# InkTime-SmartWatch.net
KiCad netlist of a schematic drawn in EAGLE
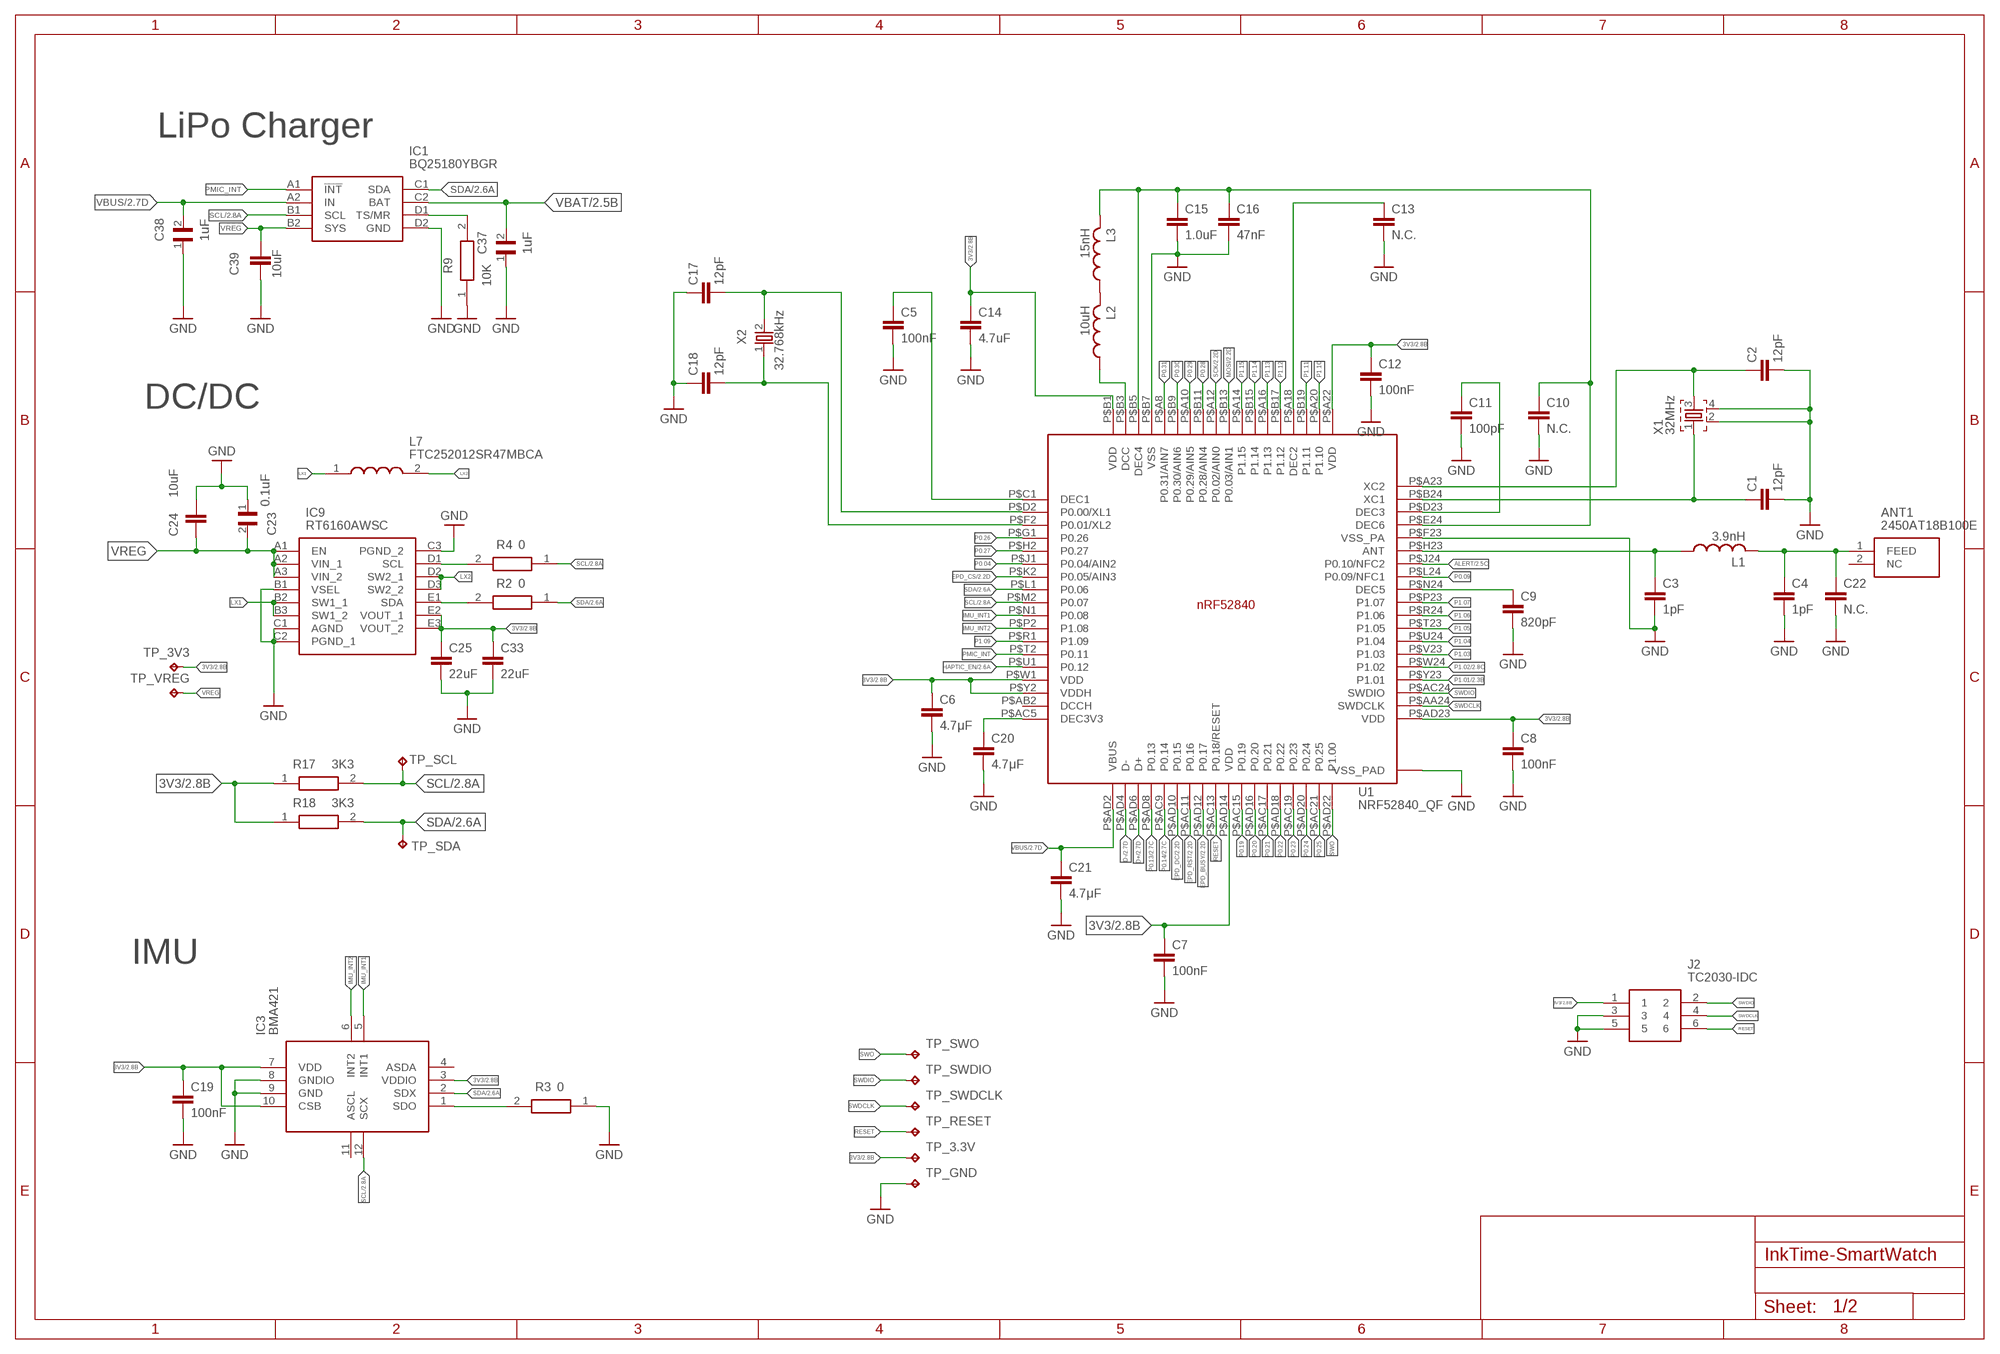
[diagram p0: schematic, sheet 1]
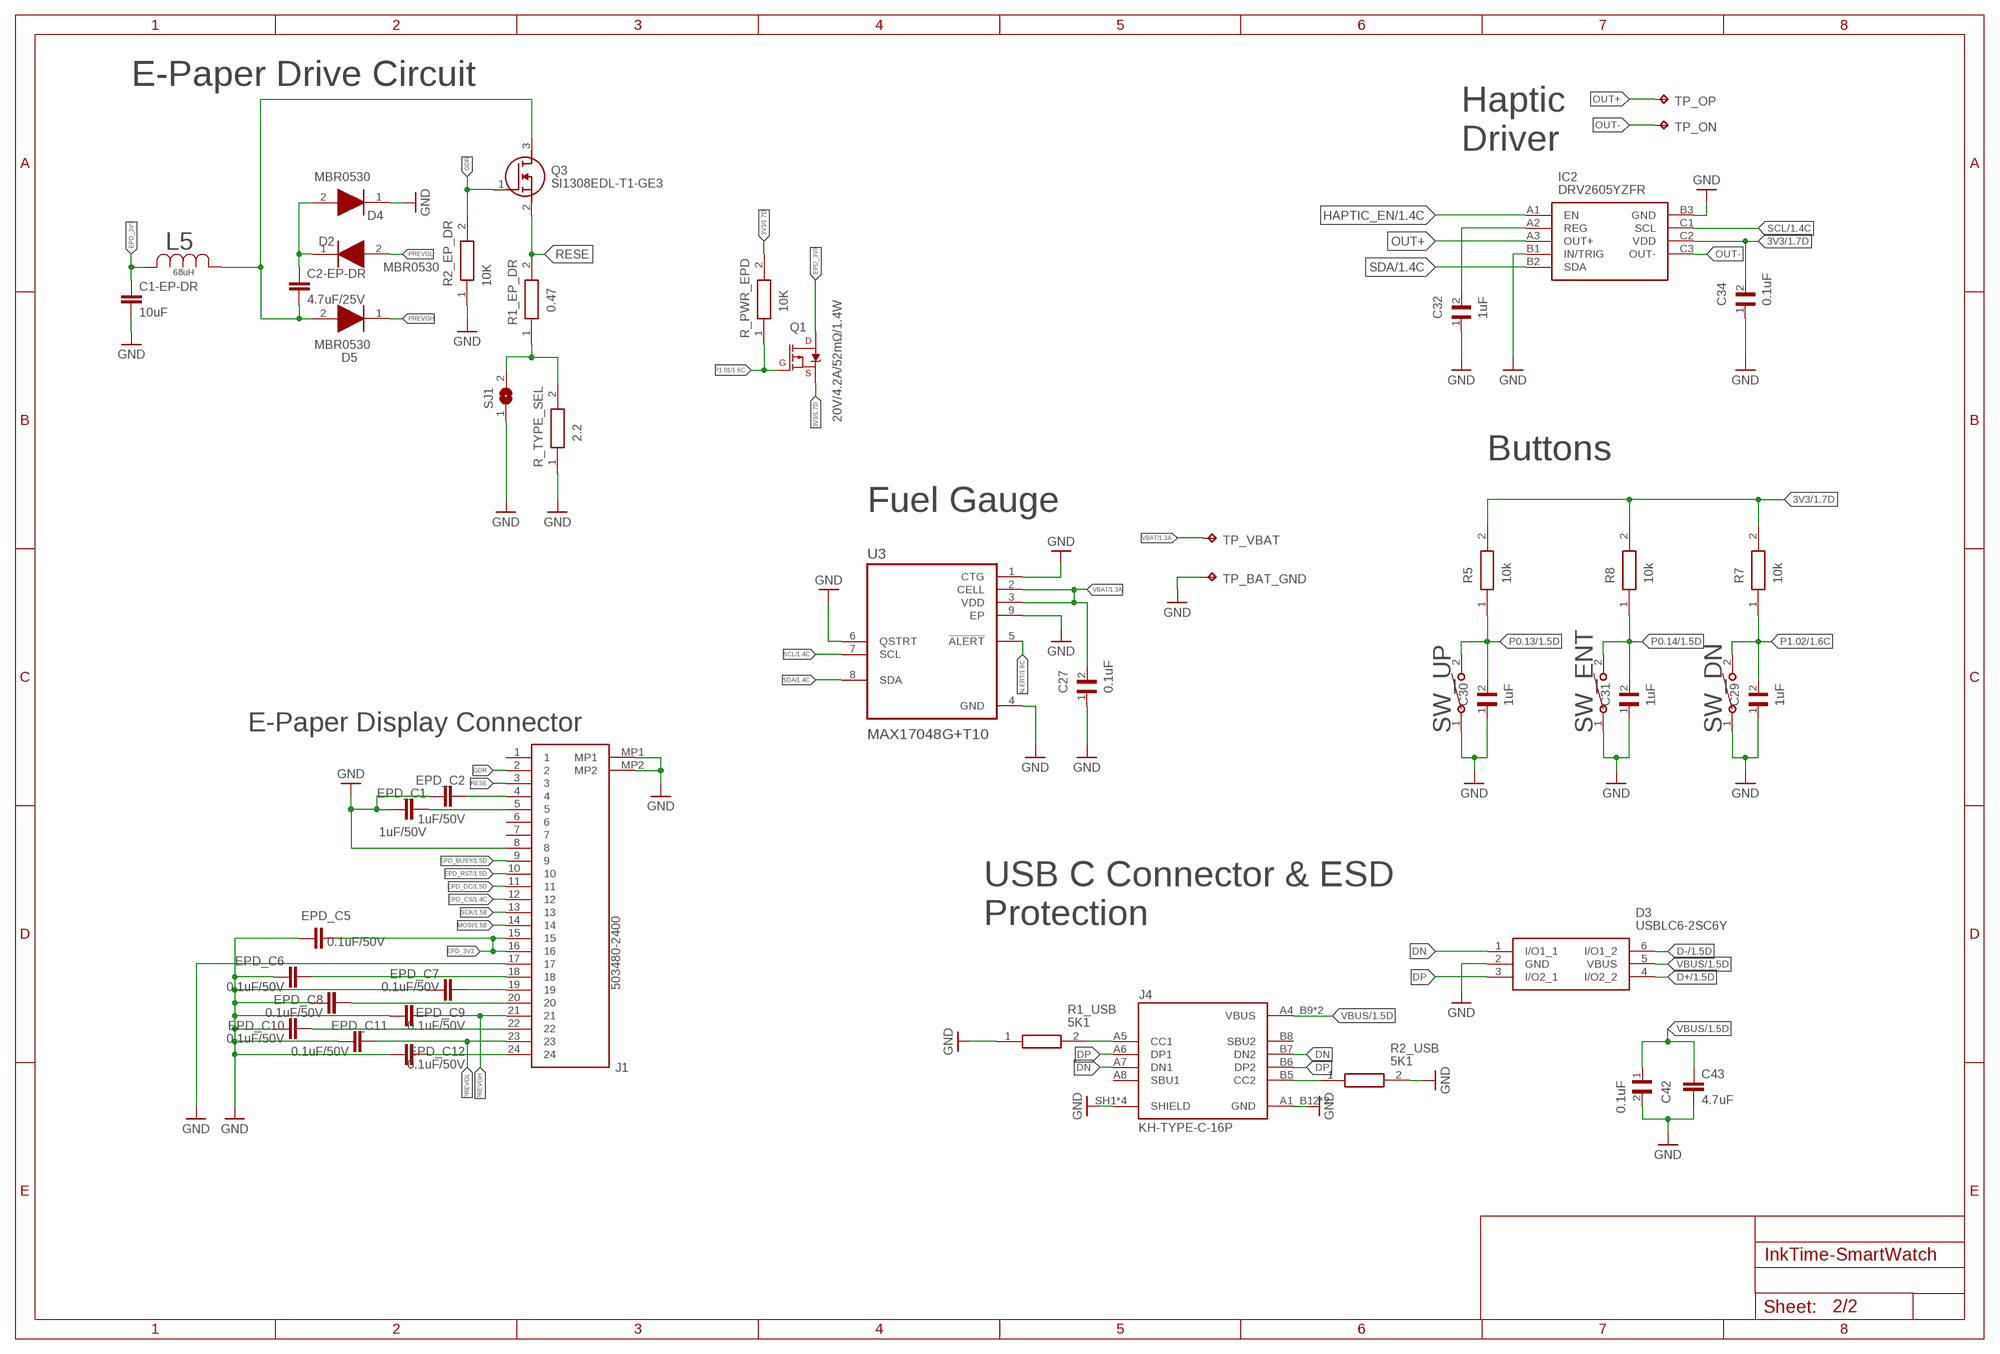
[diagram p1: schematic, sheet 2]

(export (version "E")
  (design (tool "Eeschema 10.0.6"))
  (components
    (comp (ref "C1-EP-DR")
      (value "10uF")
      (footprint "eagle-import:NORDIC_NRF_3_RESC0402_L")
      (libsource (lib "eagle-import") (part "NORDIC_NRF_3_CAPACITOR_0402_L"))
    )
    (comp (ref "C2-EP-DR")
      (value "4.7uF/25V")
      (footprint "eagle-import:NORDIC_NRF_3_RESC0402_L")
      (libsource (lib "eagle-import") (part "NORDIC_NRF_3_CAPACITOR_0402_L"))
    )
    (comp (ref "C27")
      (value "0.1uF")
      (footprint "eagle-import:GRM011R60J152KE01L_2_CAPC0201X13N")
      (fields (field (name "MF") "Murata") (field (name "MP") "GRM011R60J152KE01L"))
      (libsource (lib "eagle-import") (part "GRM011R60J152KE01L_2_GRM011R60J152KE01L"))
    )
    (comp (ref "C29")
      (value "1uF")
      (footprint "eagle-import:GRM011R60J152KE01L_2_CAPC0201X13N")
      (fields (field (name "MF") "Murata") (field (name "MP") "GRM011R60J152KE01L"))
      (libsource (lib "eagle-import") (part "GRM011R60J152KE01L_2_GRM011R60J152KE01L"))
    )
    (comp (ref "C30")
      (value "1uF")
      (footprint "eagle-import:GRM011R60J152KE01L_2_CAPC0201X13N")
      (fields (field (name "MF") "Murata") (field (name "MP") "GRM011R60J152KE01L"))
      (libsource (lib "eagle-import") (part "GRM011R60J152KE01L_2_GRM011R60J152KE01L"))
    )
    (comp (ref "C31")
      (value "1uF")
      (footprint "eagle-import:GRM011R60J152KE01L_2_CAPC0201X13N")
      (fields (field (name "MF") "Murata") (field (name "MP") "GRM011R60J152KE01L"))
      (libsource (lib "eagle-import") (part "GRM011R60J152KE01L_2_GRM011R60J152KE01L"))
    )
    (comp (ref "C32")
      (value "1uF")
      (footprint "eagle-import:GRM011R60J152KE01L_2_CAPC0201X13N")
      (fields (field (name "MF") "Murata") (field (name "MP") "GRM011R60J152KE01L"))
      (libsource (lib "eagle-import") (part "GRM011R60J152KE01L_2_GRM011R60J152KE01L"))
    )
    (comp (ref "C34")
      (value "0.1uF")
      (footprint "eagle-import:GRM011R60J152KE01L_2_CAPC0201X13N")
      (fields (field (name "MF") "Murata") (field (name "MP") "GRM011R60J152KE01L"))
      (libsource (lib "eagle-import") (part "GRM011R60J152KE01L_2_GRM011R60J152KE01L"))
    )
    (comp (ref "C42")
      (value "0.1uF")
      (footprint "eagle-import:GRM011R60J152KE01L_2_CAPC0201X13N")
      (fields (field (name "MF") "Murata") (field (name "MP") "GRM011R60J152KE01L"))
      (libsource (lib "eagle-import") (part "GRM011R60J152KE01L_2_GRM011R60J152KE01L"))
    )
    (comp (ref "C43")
      (value "4.7uF")
      (footprint "eagle-import:NORDIC_NRF_3_RESC0402_L")
      (libsource (lib "eagle-import") (part "NORDIC_NRF_3_CAPACITOR_0402_L"))
    )
    (comp (ref "D2")
      (value "MBR0530")
      (footprint "eagle-import:ESP32_C6_LIBRARY_5_SOD3716X135N")
      (fields (field (name "MF") "ON Semiconductor"))
      (libsource (lib "eagle-import") (part "ESP32_C6_LIBRARY_5_MBR0530"))
    )
    (comp (ref "D3")
      (value "USBLC6-2SC6Y")
      (footprint "eagle-import:ESP32_C6_LIBRARY_3_SOT95P280X145-6N")
      (fields (field (name "MF") "STMicroelectronics"))
      (libsource (lib "eagle-import") (part "ESP32_C6_LIBRARY_3_USBLC6-2SC6Y"))
    )
    (comp (ref "D4")
      (value "MBR0530")
      (footprint "eagle-import:ESP32_C6_LIBRARY_5_SOD3716X135N")
      (fields (field (name "MF") "ON Semiconductor"))
      (libsource (lib "eagle-import") (part "ESP32_C6_LIBRARY_5_MBR0530"))
    )
    (comp (ref "D5")
      (value "MBR0530")
      (footprint "eagle-import:ESP32_C6_LIBRARY_5_SOD3716X135N")
      (fields (field (name "MF") "ON Semiconductor"))
      (libsource (lib "eagle-import") (part "ESP32_C6_LIBRARY_5_MBR0530"))
    )
    (comp (ref "EPD_C1")
      (value "1uF/50V")
      (footprint "eagle-import:NORDIC_NRF_3_RESC0402_L")
      (libsource (lib "eagle-import") (part "NORDIC_NRF_3_CAPACITOR_0402_L"))
    )
    (comp (ref "EPD_C2")
      (value "1uF/50V")
      (footprint "eagle-import:NORDIC_NRF_3_RESC0402_L")
      (libsource (lib "eagle-import") (part "NORDIC_NRF_3_CAPACITOR_0402_L"))
    )
    (comp (ref "EPD_C5")
      (value "0.1uF/50V")
      (footprint "eagle-import:NORDIC_NRF_3_RESC0201_L")
      (libsource (lib "eagle-import") (part "NORDIC_NRF_3_CAPACITOR_0201_L"))
    )
    (comp (ref "EPD_C6")
      (value "0.1uF/50V")
      (footprint "eagle-import:NORDIC_NRF_3_RESC0402_L")
      (libsource (lib "eagle-import") (part "NORDIC_NRF_3_CAPACITOR_0402_L"))
    )
    (comp (ref "EPD_C7")
      (value "0.1uF/50V")
      (footprint "eagle-import:NORDIC_NRF_3_RESC0402_L")
      (libsource (lib "eagle-import") (part "NORDIC_NRF_3_CAPACITOR_0402_L"))
    )
    (comp (ref "EPD_C8")
      (value "0.1uF/50V")
      (footprint "eagle-import:NORDIC_NRF_3_RESC0402_L")
      (libsource (lib "eagle-import") (part "NORDIC_NRF_3_CAPACITOR_0402_L"))
    )
    (comp (ref "EPD_C9")
      (value "0.1uF/50V")
      (footprint "eagle-import:NORDIC_NRF_3_RESC0402_L")
      (libsource (lib "eagle-import") (part "NORDIC_NRF_3_CAPACITOR_0402_L"))
    )
    (comp (ref "EPD_C10")
      (value "0.1uF/50V")
      (footprint "eagle-import:NORDIC_NRF_3_RESC0402_L")
      (libsource (lib "eagle-import") (part "NORDIC_NRF_3_CAPACITOR_0402_L"))
    )
    (comp (ref "EPD_C11")
      (value "0.1uF/50V")
      (footprint "eagle-import:NORDIC_NRF_3_RESC0402_L")
      (libsource (lib "eagle-import") (part "NORDIC_NRF_3_CAPACITOR_0402_L"))
    )
    (comp (ref "EPD_C12")
      (value "0.1uF/50V")
      (footprint "eagle-import:NORDIC_NRF_3_RESC0402_L")
      (libsource (lib "eagle-import") (part "NORDIC_NRF_3_CAPACITOR_0402_L"))
    )
    (comp (ref "IC2")
      (value "DRV2605YZFR")
      (footprint "eagle-import:DRV2605YZFR_BGA9C50P3X3_144X144X62")
      (libsource (lib "eagle-import") (part "DRV2605YZFR_DRV2605YZFR"))
    )
    (comp (ref "J1")
      (value "503480-2400")
      (footprint "eagle-import:503480-2400_5034802400")
      (fields (field (name "MOUSER_PART_NUMBER") "538-503480-2400"))
      (libsource (lib "eagle-import") (part "503480-2400_503480-2400"))
    )
    (comp (ref "J4")
      (value "KH-TYPE-C-16P")
      (footprint "eagle-import:KH-TYPE-C-16P_KINGHELM_KH-TYPE-C-16P")
      (fields (field (name "MF") "kinghelm"))
      (libsource (lib "eagle-import") (part "KH-TYPE-C-16P_KH-TYPE-C-16P"))
    )
    (comp (ref "L5")
      (value "68uH")
      (footprint "eagle-import:ESP32_C6_LIBRARY_2_IND_4828-WE-TPC_WRE")
      (fields
        (field (name "MANUFACTURER_PART_NUMBER") "744043680")
        (field (name "COPYRIGHT") "Copyright (C) 2024 Ultra Librarian. All rights reserved.")
      )
      (libsource (lib "eagle-import") (part "ESP32_C6_LIBRARY_2_744043680IND_4828-WE-TPC_WRE"))
    )
    (comp (ref "Q1")
      (value "20V/4.2A/52mΩ/1.4W")
      (footprint "eagle-import:ESP32_C6_LIBRARY_4_ESP32_C6_LIBRARY_4_ESP32_C6_LIBRARY_4_ESP32_C6_LIBRARY_4_ESP32_WROVER_SPARKFUN-DISCRETESEMI_SOT23-3")
      (libsource (lib "eagle-import") (part "ESP32_C6_LIBRARY_4_ESP32_WROVER_SPARKFUN-DISCRETESEMI_MOSFET_PCH-DMG2305UX-7"))
    )
    (comp (ref "Q3")
      (value "SI1308EDL-T1-GE3")
      (footprint "eagle-import:ESP32_C6_LIBRARY_6_SOT65P210X110-3N")
      (fields (field (name "MF") "Vishay Siliconix"))
      (libsource (lib "eagle-import") (part "ESP32_C6_LIBRARY_6_SI1308EDL-T1-GE3"))
    )
    (comp (ref "R1_EP_DR")
      (value "0.47")
      (footprint "eagle-import:CPF0201D7K68C1_0201")
      (libsource (lib "eagle-import") (part "CPF0201D7K68C1_CPF0201D7K68C1"))
    )
    (comp (ref "R1_USB")
      (value "5K1")
      (footprint "eagle-import:CPF0201D7K68C1_0201")
      (libsource (lib "eagle-import") (part "CPF0201D7K68C1_CPF0201D7K68C1"))
    )
    (comp (ref "R2_EP_DR")
      (value "10K")
      (footprint "eagle-import:CPF0201D7K68C1_0201")
      (libsource (lib "eagle-import") (part "CPF0201D7K68C1_CPF0201D7K68C1"))
    )
    (comp (ref "R2_USB")
      (value "5K1")
      (footprint "eagle-import:CPF0201D7K68C1_0201")
      (libsource (lib "eagle-import") (part "CPF0201D7K68C1_CPF0201D7K68C1"))
    )
    (comp (ref "R5")
      (value "10k")
      (footprint "eagle-import:CPF0201D7K68C1_0201")
      (libsource (lib "eagle-import") (part "CPF0201D7K68C1_CPF0201D7K68C1"))
    )
    (comp (ref "R7")
      (value "10k")
      (footprint "eagle-import:CPF0201D7K68C1_0201")
      (libsource (lib "eagle-import") (part "CPF0201D7K68C1_CPF0201D7K68C1"))
    )
    (comp (ref "R8")
      (value "10k")
      (footprint "eagle-import:CPF0201D7K68C1_0201")
      (libsource (lib "eagle-import") (part "CPF0201D7K68C1_CPF0201D7K68C1"))
    )
    (comp (ref "R_PWR_EPD")
      (value "10K")
      (footprint "eagle-import:CPF0201D7K68C1_0201")
      (libsource (lib "eagle-import") (part "CPF0201D7K68C1_CPF0201D7K68C1"))
    )
    (comp (ref "R_TYPE_SEL")
      (value "2.2")
      (footprint "eagle-import:CPF0201D7K68C1_0201")
      (libsource (lib "eagle-import") (part "CPF0201D7K68C1_CPF0201D7K68C1"))
    )
    (comp (ref "SJ1")
      (value "ESP32_C6_LIBRARY_7_JUMPER_SJ")
      (footprint "eagle-import:ESP32_C6_LIBRARY_7_JUMPER_SJ")
      (libsource (lib "eagle-import") (part "ESP32_C6_LIBRARY_7_JUMPER_SJ"))
    )
    (comp (ref "SW_DN")
      (value "2025-10-22_07-23-44_LIBRARY_EVP-AKE31ASW_EVP-AKE31A_PAN")
      (footprint "eagle-import:2025-10-22_07-23-44_LIBRARY_SW_EVP-AKE31A_PAN")
      (fields
        (field (name "MANUFACTURER_PART_NUMBER") "EVP-AKE31A")
        (field (name "COPYRIGHT") "Copyright (C) 2025 Ultra Librarian. All rights reserved.")
      )
      (libsource (lib "eagle-import") (part "2025-10-22_07-23-44_LIBRARY_EVP-AKE31ASW_EVP-AKE31A_PAN"))
    )
    (comp (ref "SW_ENT")
      (value "2025-10-22_07-23-44_LIBRARY_EVP-AKE31ASW_EVP-AKE31A_PAN")
      (footprint "eagle-import:2025-10-22_07-23-44_LIBRARY_SW_EVP-AKE31A_PAN")
      (fields
        (field (name "MANUFACTURER_PART_NUMBER") "EVP-AKE31A")
        (field (name "COPYRIGHT") "Copyright (C) 2025 Ultra Librarian. All rights reserved.")
      )
      (libsource (lib "eagle-import") (part "2025-10-22_07-23-44_LIBRARY_EVP-AKE31ASW_EVP-AKE31A_PAN"))
    )
    (comp (ref "SW_UP")
      (value "2025-10-22_07-23-44_LIBRARY_EVP-AKE31ASW_EVP-AKE31A_PAN")
      (footprint "eagle-import:2025-10-22_07-23-44_LIBRARY_SW_EVP-AKE31A_PAN")
      (fields
        (field (name "MANUFACTURER_PART_NUMBER") "EVP-AKE31A")
        (field (name "COPYRIGHT") "Copyright (C) 2025 Ultra Librarian. All rights reserved.")
      )
      (libsource (lib "eagle-import") (part "2025-10-22_07-23-44_LIBRARY_EVP-AKE31ASW_EVP-AKE31A_PAN"))
    )
    (comp (ref "TP_BAT_GND")
      (value "HECTOR_WATCH_1_TPTP20R")
      (footprint "eagle-import:HECTOR_WATCH_1_TP20R")
      (libsource (lib "eagle-import") (part "HECTOR_WATCH_1_TPTP20R"))
    )
    (comp (ref "TP_ON")
      (value "HECTOR_WATCH_1_TPTP20R")
      (footprint "eagle-import:HECTOR_WATCH_1_TP20R")
      (libsource (lib "eagle-import") (part "HECTOR_WATCH_1_TPTP20R"))
    )
    (comp (ref "TP_OP")
      (value "HECTOR_WATCH_1_TPTP20R")
      (footprint "eagle-import:HECTOR_WATCH_1_TP20R")
      (libsource (lib "eagle-import") (part "HECTOR_WATCH_1_TPTP20R"))
    )
    (comp (ref "TP_VBAT")
      (value "HECTOR_WATCH_1_TPTP20R")
      (footprint "eagle-import:HECTOR_WATCH_1_TP20R")
      (libsource (lib "eagle-import") (part "HECTOR_WATCH_1_TPTP20R"))
    )
    (comp (ref "U3")
      (value "MAX17048G+T10")
      (footprint "eagle-import:ESP32_C6_LIBRARY_SON50P200X200X80-9N")
      (fields (field (name "MF") "Analog Devices"))
      (libsource (lib "eagle-import") (part "ESP32_C6_LIBRARY_MAX17048G+T10"))
    )
    (comp (ref "ANT1")
      (value "2450AT18B100E")
      (footprint "eagle-import:2450AT18B100E_ANTC3216X140N")
      (fields (field (name "MOUSER_PART_NUMBER") "609-2450AT18B100E"))
      (libsource (lib "eagle-import") (part "2450AT18B100E_2450AT18B100E"))
    )
    (comp (ref "C1")
      (value "12pF")
      (footprint "eagle-import:NORDIC_NRF_3_RESC0201_L")
      (libsource (lib "eagle-import") (part "NORDIC_NRF_3_CAPACITOR_0201_L"))
    )
    (comp (ref "C2")
      (value "12pF")
      (footprint "eagle-import:NORDIC_NRF_3_RESC0201_L")
      (libsource (lib "eagle-import") (part "NORDIC_NRF_3_CAPACITOR_0201_L"))
    )
    (comp (ref "C3")
      (value "1pF")
      (footprint "eagle-import:NORDIC_NRF_3_RESC0201_L")
      (libsource (lib "eagle-import") (part "NORDIC_NRF_3_CAPACITOR_0201_L"))
    )
    (comp (ref "C4")
      (value "1pF")
      (footprint "eagle-import:NORDIC_NRF_3_RESC0201_L")
      (libsource (lib "eagle-import") (part "NORDIC_NRF_3_CAPACITOR_0201_L"))
    )
    (comp (ref "C5")
      (value "100nF")
      (footprint "eagle-import:NORDIC_NRF_3_RESC0201_L")
      (libsource (lib "eagle-import") (part "NORDIC_NRF_3_CAPACITOR_0201_L"))
    )
    (comp (ref "C6")
      (value "4.7μF")
      (footprint "eagle-import:PERFECT_0402_0402")
      (libsource (lib "eagle-import") (part "PERFECT_0402_CAP_0402"))
    )
    (comp (ref "C7")
      (value "100nF")
      (footprint "eagle-import:NORDIC_NRF_3_RESC0201_L")
      (libsource (lib "eagle-import") (part "NORDIC_NRF_3_CAPACITOR_0201_L"))
    )
    (comp (ref "C8")
      (value "100nF")
      (footprint "eagle-import:NORDIC_NRF_3_RESC0201_L")
      (libsource (lib "eagle-import") (part "NORDIC_NRF_3_CAPACITOR_0201_L"))
    )
    (comp (ref "C9")
      (value "820pF")
      (footprint "eagle-import:NORDIC_NRF_3_RESC0201_L")
      (libsource (lib "eagle-import") (part "NORDIC_NRF_3_CAPACITOR_0201_L"))
    )
    (comp (ref "C10")
      (value "N.C.")
      (footprint "eagle-import:NORDIC_NRF_3_RESC0201_L")
      (libsource (lib "eagle-import") (part "NORDIC_NRF_3_CAPACITOR_0201_L"))
    )
    (comp (ref "C11")
      (value "100pF")
      (footprint "eagle-import:NORDIC_NRF_3_RESC0201_L")
      (libsource (lib "eagle-import") (part "NORDIC_NRF_3_CAPACITOR_0201_L"))
    )
    (comp (ref "C12")
      (value "100nF")
      (footprint "eagle-import:NORDIC_NRF_3_RESC0201_L")
      (libsource (lib "eagle-import") (part "NORDIC_NRF_3_CAPACITOR_0201_L"))
    )
    (comp (ref "C13")
      (value "N.C.")
      (footprint "eagle-import:NORDIC_NRF_3_RESC0201_L")
      (libsource (lib "eagle-import") (part "NORDIC_NRF_3_CAPACITOR_0201_L"))
    )
    (comp (ref "C14")
      (value "4.7uF")
      (footprint "eagle-import:NORDIC_NRF_3_RESC0402_L")
      (libsource (lib "eagle-import") (part "NORDIC_NRF_3_CAPACITOR_0402_L"))
    )
    (comp (ref "C15")
      (value "1.0uF")
      (footprint "eagle-import:PERFECT_0402_0402")
      (libsource (lib "eagle-import") (part "PERFECT_0402_CAP_0402"))
    )
    (comp (ref "C16")
      (value "47nF")
      (footprint "eagle-import:PERFECT_0402_0402")
      (libsource (lib "eagle-import") (part "PERFECT_0402_CAP_0402"))
    )
    (comp (ref "C17")
      (value "12pF")
      (footprint "eagle-import:NORDIC_NRF_3_RESC0201_L")
      (libsource (lib "eagle-import") (part "NORDIC_NRF_3_CAPACITOR_0201_L"))
    )
    (comp (ref "C18")
      (value "12pF")
      (footprint "eagle-import:NORDIC_NRF_3_RESC0201_L")
      (libsource (lib "eagle-import") (part "NORDIC_NRF_3_CAPACITOR_0201_L"))
    )
    (comp (ref "C19")
      (value "100nF")
      (footprint "eagle-import:NORDIC_NRF_3_RESC0201_L")
      (libsource (lib "eagle-import") (part "NORDIC_NRF_3_CAPACITOR_0201_L"))
    )
    (comp (ref "C20")
      (value "4.7μF")
      (footprint "eagle-import:PERFECT_0402_0402")
      (libsource (lib "eagle-import") (part "PERFECT_0402_CAP_0402"))
    )
    (comp (ref "C21")
      (value "4.7μF")
      (footprint "eagle-import:PERFECT_0402_0402")
      (libsource (lib "eagle-import") (part "PERFECT_0402_CAP_0402"))
    )
    (comp (ref "C22")
      (value "N.C.")
      (footprint "eagle-import:NORDIC_NRF_3_RESC0201_L")
      (libsource (lib "eagle-import") (part "NORDIC_NRF_3_CAPACITOR_0201_L"))
    )
    (comp (ref "C23")
      (value "0.1uF")
      (footprint "eagle-import:GRM011R60J152KE01L_2_CAPC0201X13N")
      (fields (field (name "MF") "Murata") (field (name "MP") "GRM011R60J152KE01L"))
      (libsource (lib "eagle-import") (part "GRM011R60J152KE01L_2_GRM011R60J152KE01L"))
    )
    (comp (ref "C24")
      (value "10uF")
      (footprint "eagle-import:PERFECT_0402_0402")
      (libsource (lib "eagle-import") (part "PERFECT_0402_CAP_0402"))
    )
    (comp (ref "C25")
      (value "22uF")
      (footprint "eagle-import:PERFECT_0402_0402")
      (libsource (lib "eagle-import") (part "PERFECT_0402_CAP_0402"))
    )
    (comp (ref "C33")
      (value "22uF")
      (footprint "eagle-import:PERFECT_0402_0402")
      (libsource (lib "eagle-import") (part "PERFECT_0402_CAP_0402"))
    )
    (comp (ref "C37")
      (value "1uF")
      (footprint "eagle-import:GRM011R60J152KE01L_2_CAPC0201X13N")
      (fields (field (name "MF") "Murata") (field (name "MP") "GRM011R60J152KE01L"))
      (libsource (lib "eagle-import") (part "GRM011R60J152KE01L_2_GRM011R60J152KE01L"))
    )
    (comp (ref "C38")
      (value "1uF")
      (footprint "eagle-import:GRM011R60J152KE01L_2_CAPC0201X13N")
      (fields (field (name "MF") "Murata") (field (name "MP") "GRM011R60J152KE01L"))
      (libsource (lib "eagle-import") (part "GRM011R60J152KE01L_2_GRM011R60J152KE01L"))
    )
    (comp (ref "C39")
      (value "10uF")
      (footprint "eagle-import:PERFECT_0402_0402")
      (libsource (lib "eagle-import") (part "PERFECT_0402_CAP_0402"))
    )
    (comp (ref "IC1")
      (value "BQ25180YBGR")
      (footprint "eagle-import:BQ25180YBGR_BGA8C40P2X4_100X155X50")
      (fields (field (name "MOUSER_PART_NUMBER") "595-BQ25180YBGR"))
      (libsource (lib "eagle-import") (part "BQ25180YBGR_BQ25180YBGR"))
    )
    (comp (ref "IC3")
      (value "BMA421")
      (footprint "eagle-import:BMA423_BMA423")
      (fields (field (name "ARROW_PART_NUMBER") "BMA423") (field (name "MOUSER_PART_NUMBER") "262-BMA423"))
      (libsource (lib "eagle-import") (part "BMA423_BMA423"))
    )
    (comp (ref "IC9")
      (value "RT6160AWSC")
      (footprint "eagle-import:RT6160AWSC_BGA15C40P3X5_140X230X60")
      (fields (field (name "MOUSER_PART_NUMBER") "835-RT6160AWSC"))
      (libsource (lib "eagle-import") (part "RT6160AWSC_RT6160AWSC"))
    )
    (comp (ref "J2")
      (value "TC2030-IDC")
      (footprint "eagle-import:TC2030-IDC_TC2030IDC")
      (libsource (lib "eagle-import") (part "TC2030-IDC_TC2030-IDC"))
    )
    (comp (ref "L1")
      (value "3.9nH")
      (footprint "eagle-import:NORDIC_NRF_2_RESC0402_L")
      (libsource (lib "eagle-import") (part "NORDIC_NRF_2_INDUCTOR_0402_L"))
    )
    (comp (ref "L2")
      (value "10uH")
      (footprint "eagle-import:NORDIC_NRF_2_RESC0402_L")
      (libsource (lib "eagle-import") (part "NORDIC_NRF_2_INDUCTOR_0402_L"))
    )
    (comp (ref "L3")
      (value "15nH")
      (footprint "eagle-import:NORDIC_NRF_2_RESC0402_L")
      (libsource (lib "eagle-import") (part "NORDIC_NRF_2_INDUCTOR_0402_L"))
    )
    (comp (ref "L7")
      (value "FTC252012SR47MBCA")
      (footprint "eagle-import:MLP2016SR47MT0S1_INDC2016X100N")
      (libsource (lib "eagle-import") (part "MLP2016SR47MT0S1_FTC252012SR47MBCA"))
    )
    (comp (ref "R2")
      (value "0")
      (footprint "eagle-import:CPF0201D7K68C1_0201")
      (libsource (lib "eagle-import") (part "CPF0201D7K68C1_CPF0201D7K68C1"))
    )
    (comp (ref "R3")
      (value "0")
      (footprint "eagle-import:CPF0201D7K68C1_0201")
      (libsource (lib "eagle-import") (part "CPF0201D7K68C1_CPF0201D7K68C1"))
    )
    (comp (ref "R4")
      (value "0")
      (footprint "eagle-import:CPF0201D7K68C1_0201")
      (libsource (lib "eagle-import") (part "CPF0201D7K68C1_CPF0201D7K68C1"))
    )
    (comp (ref "R9")
      (value "10K")
      (footprint "eagle-import:CPF0201D7K68C1_0201")
      (libsource (lib "eagle-import") (part "CPF0201D7K68C1_CPF0201D7K68C1"))
    )
    (comp (ref "R17")
      (value "3K3")
      (footprint "eagle-import:CPF0201D7K68C1_0201")
      (libsource (lib "eagle-import") (part "CPF0201D7K68C1_CPF0201D7K68C1"))
    )
    (comp (ref "R18")
      (value "3K3")
      (footprint "eagle-import:CPF0201D7K68C1_0201")
      (libsource (lib "eagle-import") (part "CPF0201D7K68C1_CPF0201D7K68C1"))
    )
    (comp (ref "TP_3.3V")
      (value "HECTOR_WATCH_1_TPTP20R")
      (footprint "eagle-import:HECTOR_WATCH_1_TP20R")
      (libsource (lib "eagle-import") (part "HECTOR_WATCH_1_TPTP20R"))
    )
    (comp (ref "TP_3V3")
      (value "HECTOR_WATCH_1_TPTP20R")
      (footprint "eagle-import:HECTOR_WATCH_1_TP20R")
      (libsource (lib "eagle-import") (part "HECTOR_WATCH_1_TPTP20R"))
    )
    (comp (ref "TP_GND")
      (value "HECTOR_WATCH_1_TPTP20R")
      (footprint "eagle-import:HECTOR_WATCH_1_TP20R")
      (libsource (lib "eagle-import") (part "HECTOR_WATCH_1_TPTP20R"))
    )
    (comp (ref "TP_RESET")
      (value "HECTOR_WATCH_1_TPTP20R")
      (footprint "eagle-import:HECTOR_WATCH_1_TP20R")
      (libsource (lib "eagle-import") (part "HECTOR_WATCH_1_TPTP20R"))
    )
    (comp (ref "TP_SCL")
      (value "HECTOR_WATCH_1_TPTP20R")
      (footprint "eagle-import:HECTOR_WATCH_1_TP20R")
      (libsource (lib "eagle-import") (part "HECTOR_WATCH_1_TPTP20R"))
    )
    (comp (ref "TP_SDA")
      (value "HECTOR_WATCH_1_TPTP20R")
      (footprint "eagle-import:HECTOR_WATCH_1_TP20R")
      (libsource (lib "eagle-import") (part "HECTOR_WATCH_1_TPTP20R"))
    )
    (comp (ref "TP_SWDCLK")
      (value "HECTOR_WATCH_1_TPTP20R")
      (footprint "eagle-import:HECTOR_WATCH_1_TP20R")
      (libsource (lib "eagle-import") (part "HECTOR_WATCH_1_TPTP20R"))
    )
    (comp (ref "TP_SWDIO")
      (value "HECTOR_WATCH_1_TPTP20R")
      (footprint "eagle-import:HECTOR_WATCH_1_TP20R")
      (libsource (lib "eagle-import") (part "HECTOR_WATCH_1_TPTP20R"))
    )
    (comp (ref "TP_SWO")
      (value "HECTOR_WATCH_1_TPTP20R")
      (footprint "eagle-import:HECTOR_WATCH_1_TP20R")
      (libsource (lib "eagle-import") (part "HECTOR_WATCH_1_TPTP20R"))
    )
    (comp (ref "TP_VREG")
      (value "HECTOR_WATCH_1_TPTP20R")
      (footprint "eagle-import:HECTOR_WATCH_1_TP20R")
      (libsource (lib "eagle-import") (part "HECTOR_WATCH_1_TPTP20R"))
    )
    (comp (ref "U1")
      (value "NRF52840_QF")
      (footprint "eagle-import:NORDIC_NRF_4_AQFN50P700X700X85_HS-74N")
      (libsource (lib "eagle-import") (part "NORDIC_NRF_4_NRF52840_QF"))
    )
    (comp (ref "X1")
      (value "32MHz")
      (footprint "eagle-import:NORDIC_NRF_BT-XTAL_2016_N")
      (libsource (lib "eagle-import") (part "NORDIC_NRF_XTAL_32MHZ"))
    )
    (comp (ref "X2")
      (value "32.768kHz")
      (footprint "eagle-import:NORDIC_NRF_1_XTAL_3215_N")
      (libsource (lib "eagle-import") (part "NORDIC_NRF_1_XTAL_32KHZ"))
    )
  )
  (nets
    (net (code "1") (name "3V3") (class "Default")
      (node (ref "C12") (pin "1") (pinfunction "1_1") (pintype "passive"))
      (node (ref "C14") (pin "1") (pinfunction "1_1") (pintype "passive"))
      (node (ref "C19") (pin "1") (pinfunction "1_1") (pintype "passive"))
      (node (ref "C25") (pin "1") (pinfunction "1_1") (pintype "passive"))
      (node (ref "C33") (pin "1") (pinfunction "1_1") (pintype "passive"))
      (node (ref "C34") (pin "2") (pinfunction "2_2") (pintype "passive"))
      (node (ref "C6") (pin "1") (pinfunction "1_1") (pintype "passive"))
      (node (ref "C7") (pin "1") (pinfunction "1_1") (pintype "passive"))
      (node (ref "C8") (pin "1") (pinfunction "1_1") (pintype "passive"))
      (node (ref "IC2") (pin "C2") (pinfunction "VDD_C2") (pintype "bidirectional"))
      (node (ref "IC3") (pin "10") (pinfunction "CSB_10") (pintype "bidirectional"))
      (node (ref "IC3") (pin "3") (pinfunction "VDDIO_3") (pintype "bidirectional"))
      (node (ref "IC3") (pin "7") (pinfunction "VDD_7") (pintype "bidirectional"))
      (node (ref "IC9") (pin "E2") (pinfunction "VOUT_1_E2") (pintype "bidirectional"))
      (node (ref "IC9") (pin "E3") (pinfunction "VOUT_2_E3") (pintype "bidirectional"))
      (node (ref "J2") (pin "1") (pinfunction "1_1") (pintype "bidirectional"))
      (node (ref "Q1") (pin "2") (pinfunction "S_2") (pintype "bidirectional"))
      (node (ref "R17") (pin "1") (pinfunction "1_1") (pintype "bidirectional"))
      (node (ref "R18") (pin "1") (pinfunction "1_1") (pintype "bidirectional"))
      (node (ref "R5") (pin "2") (pinfunction "2_2") (pintype "bidirectional"))
      (node (ref "R7") (pin "2") (pinfunction "2_2") (pintype "bidirectional"))
      (node (ref "R8") (pin "2") (pinfunction "2_2") (pintype "bidirectional"))
      (node (ref "R_PWR_EPD") (pin "2") (pinfunction "2_2") (pintype "bidirectional"))
      (node (ref "TP_3.3V") (pin "TP") (pinfunction "TP_TP") (pintype "input"))
      (node (ref "TP_3V3") (pin "TP") (pinfunction "TP_TP") (pintype "input"))
      (node (ref "U1") (pin "P$A22") (pinfunction "VDD_P$A22") (pintype "power_in"))
      (node (ref "U1") (pin "P$AD14") (pinfunction "VDD_P$AD14") (pintype "power_in"))
      (node (ref "U1") (pin "P$AD23") (pinfunction "VDD_P$AD23") (pintype "power_in"))
      (node (ref "U1") (pin "P$B1") (pinfunction "VDD_P$B1") (pintype "power_in"))
      (node (ref "U1") (pin "P$W1") (pinfunction "VDD_P$W1") (pintype "power_in"))
      (node (ref "U1") (pin "P$Y2") (pinfunction "VDDH_P$Y2") (pintype "power_in"))
    )
    (net (code "2") (name "ALERT") (class "Default")
      (node (ref "U1") (pin "P$J24") (pinfunction "P0.10/NFC2_P$J24") (pintype "bidirectional"))
      (node (ref "U3") (pin "5") (pinfunction "~{ALERT}_5") (pintype "output"))
    )
    (net (code "3") (name "D+") (class "Default")
      (node (ref "D3") (pin "4") (pinfunction "I/O2_2_4") (pintype "bidirectional"))
      (node (ref "U1") (pin "P$AD6") (pinfunction "D+_P$AD6") (pintype "bidirectional"))
    )
    (net (code "4") (name "D-") (class "Default")
      (node (ref "D3") (pin "6") (pinfunction "I/O1_2_6") (pintype "bidirectional"))
      (node (ref "U1") (pin "P$AD4") (pinfunction "D-_P$AD4") (pintype "bidirectional"))
    )
    (net (code "5") (name "DN") (class "Default")
      (node (ref "D3") (pin "1") (pinfunction "I/O1_1_1") (pintype "bidirectional"))
      (node (ref "J4") (pin "A7") (pinfunction "DN1_A7") (pintype "bidirectional"))
      (node (ref "J4") (pin "B7") (pinfunction "DN2_B7") (pintype "bidirectional"))
    )
    (net (code "6") (name "DP") (class "Default")
      (node (ref "D3") (pin "3") (pinfunction "I/O2_1_3") (pintype "bidirectional"))
      (node (ref "J4") (pin "A6") (pinfunction "DP1_A6") (pintype "bidirectional"))
      (node (ref "J4") (pin "B6") (pinfunction "DP2_B6") (pintype "bidirectional"))
    )
    (net (code "7") (name "EPD_3V3") (class "Default")
      (node (ref "C1-EP-DR") (pin "1") (pinfunction "1_1") (pintype "passive"))
      (node (ref "EPD_C5") (pin "1") (pinfunction "1_1") (pintype "passive"))
      (node (ref "J1") (pin "15") (pinfunction "15_15") (pintype "bidirectional"))
      (node (ref "J1") (pin "16") (pinfunction "16_16") (pintype "bidirectional"))
      (node (ref "L5") (pin "2") (pinfunction "2_2") (pintype "passive"))
      (node (ref "Q1") (pin "3") (pinfunction "D_3") (pintype "bidirectional"))
    )
    (net (code "8") (name "EPD_BUSY") (class "Default")
      (node (ref "J1") (pin "9") (pinfunction "9_9") (pintype "bidirectional"))
      (node (ref "U1") (pin "P$AD12") (pinfunction "P0.17_P$AD12") (pintype "bidirectional"))
    )
    (net (code "9") (name "EPD_CS") (class "Default")
      (node (ref "J1") (pin "12") (pinfunction "12_12") (pintype "bidirectional"))
      (node (ref "U1") (pin "P$K2") (pinfunction "P0.05/AIN3_P$K2") (pintype "bidirectional"))
    )
    (net (code "10") (name "EPD_DC") (class "Default")
      (node (ref "J1") (pin "11") (pinfunction "11_11") (pintype "bidirectional"))
      (node (ref "U1") (pin "P$AD10") (pinfunction "P0.15_P$AD10") (pintype "bidirectional"))
    )
    (net (code "11") (name "EPD_RST") (class "Default")
      (node (ref "J1") (pin "10") (pinfunction "10_10") (pintype "bidirectional"))
      (node (ref "U1") (pin "P$AC11") (pinfunction "P0.16_P$AC11") (pintype "bidirectional"))
    )
    (net (code "12") (name "GDR") (class "Default")
      (node (ref "J1") (pin "2") (pinfunction "2_2") (pintype "bidirectional"))
      (node (ref "Q3") (pin "1") (pinfunction "G_1") (pintype "bidirectional"))
      (node (ref "R2_EP_DR") (pin "2") (pinfunction "2_2") (pintype "bidirectional"))
    )
    (net (code "13") (name "GND") (class "Default")
      (node (ref "C1") (pin "2") (pinfunction "2_2") (pintype "passive"))
      (node (ref "C1-EP-DR") (pin "2") (pinfunction "2_2") (pintype "passive"))
      (node (ref "C10") (pin "2") (pinfunction "2_2") (pintype "passive"))
      (node (ref "C11") (pin "2") (pinfunction "2_2") (pintype "passive"))
      (node (ref "C12") (pin "2") (pinfunction "2_2") (pintype "passive"))
      (node (ref "C13") (pin "2") (pinfunction "2_2") (pintype "passive"))
      (node (ref "C14") (pin "2") (pinfunction "2_2") (pintype "passive"))
      (node (ref "C15") (pin "2") (pinfunction "2_2") (pintype "passive"))
      (node (ref "C16") (pin "2") (pinfunction "2_2") (pintype "passive"))
      (node (ref "C17") (pin "1") (pinfunction "1_1") (pintype "passive"))
      (node (ref "C18") (pin "1") (pinfunction "1_1") (pintype "passive"))
      (node (ref "C19") (pin "2") (pinfunction "2_2") (pintype "passive"))
      (node (ref "C2") (pin "2") (pinfunction "2_2") (pintype "passive"))
      (node (ref "C20") (pin "2") (pinfunction "2_2") (pintype "passive"))
      (node (ref "C21") (pin "2") (pinfunction "2_2") (pintype "passive"))
      (node (ref "C22") (pin "2") (pinfunction "2_2") (pintype "passive"))
      (node (ref "C23") (pin "1") (pinfunction "1_1") (pintype "passive"))
      (node (ref "C24") (pin "1") (pinfunction "1_1") (pintype "passive"))
      (node (ref "C25") (pin "2") (pinfunction "2_2") (pintype "passive"))
      (node (ref "C27") (pin "1") (pinfunction "1_1") (pintype "passive"))
      (node (ref "C29") (pin "1") (pinfunction "1_1") (pintype "passive"))
      (node (ref "C3") (pin "2") (pinfunction "2_2") (pintype "passive"))
      (node (ref "C30") (pin "1") (pinfunction "1_1") (pintype "passive"))
      (node (ref "C31") (pin "1") (pinfunction "1_1") (pintype "passive"))
      (node (ref "C32") (pin "1") (pinfunction "1_1") (pintype "passive"))
      (node (ref "C33") (pin "2") (pinfunction "2_2") (pintype "passive"))
      (node (ref "C34") (pin "1") (pinfunction "1_1") (pintype "passive"))
      (node (ref "C37") (pin "1") (pinfunction "1_1") (pintype "passive"))
      (node (ref "C38") (pin "1") (pinfunction "1_1") (pintype "passive"))
      (node (ref "C39") (pin "2") (pinfunction "2_2") (pintype "passive"))
      (node (ref "C4") (pin "2") (pinfunction "2_2") (pintype "passive"))
      (node (ref "C42") (pin "2") (pinfunction "2_2") (pintype "passive"))
      (node (ref "C43") (pin "2") (pinfunction "2_2") (pintype "passive"))
      (node (ref "C5") (pin "2") (pinfunction "2_2") (pintype "passive"))
      (node (ref "C6") (pin "2") (pinfunction "2_2") (pintype "passive"))
      (node (ref "C7") (pin "2") (pinfunction "2_2") (pintype "passive"))
      (node (ref "C8") (pin "2") (pinfunction "2_2") (pintype "passive"))
      (node (ref "C9") (pin "2") (pinfunction "2_2") (pintype "passive"))
      (node (ref "D3") (pin "2") (pinfunction "GND_2") (pintype "bidirectional"))
      (node (ref "D4") (pin "1") (pinfunction "K_1") (pintype "bidirectional"))
      (node (ref "EPD_C1") (pin "1") (pinfunction "1_1") (pintype "passive"))
      (node (ref "EPD_C10") (pin "1") (pinfunction "1_1") (pintype "passive"))
      (node (ref "EPD_C11") (pin "1") (pinfunction "1_1") (pintype "passive"))
      (node (ref "EPD_C12") (pin "1") (pinfunction "1_1") (pintype "passive"))
      (node (ref "EPD_C2") (pin "1") (pinfunction "1_1") (pintype "passive"))
      (node (ref "EPD_C5") (pin "2") (pinfunction "2_2") (pintype "passive"))
      (node (ref "EPD_C6") (pin "1") (pinfunction "1_1") (pintype "passive"))
      (node (ref "EPD_C7") (pin "1") (pinfunction "1_1") (pintype "passive"))
      (node (ref "EPD_C8") (pin "1") (pinfunction "1_1") (pintype "passive"))
      (node (ref "EPD_C9") (pin "1") (pinfunction "1_1") (pintype "passive"))
      (node (ref "IC1") (pin "D2") (pinfunction "GND_D2") (pintype "bidirectional"))
      (node (ref "IC2") (pin "B1") (pinfunction "IN/TRIG_B1") (pintype "bidirectional"))
      (node (ref "IC2") (pin "B3") (pinfunction "GND_B3") (pintype "bidirectional"))
      (node (ref "IC3") (pin "8") (pinfunction "GNDIO_8") (pintype "bidirectional"))
      (node (ref "IC3") (pin "9") (pinfunction "GND_9") (pintype "bidirectional"))
      (node (ref "IC9") (pin "B1") (pinfunction "VSEL_B1") (pintype "bidirectional"))
      (node (ref "IC9") (pin "C1") (pinfunction "AGND_C1") (pintype "bidirectional"))
      (node (ref "IC9") (pin "C2") (pinfunction "PGND_1_C2") (pintype "bidirectional"))
      (node (ref "IC9") (pin "C3") (pinfunction "PGND_2_C3") (pintype "bidirectional"))
      (node (ref "J1") (pin "17") (pinfunction "17_17") (pintype "bidirectional"))
      (node (ref "J1") (pin "8") (pinfunction "8_8") (pintype "bidirectional"))
      (node (ref "J1") (pin "MP1") (pinfunction "MP1_MP1") (pintype "bidirectional"))
      (node (ref "J1") (pin "MP2") (pinfunction "MP2_MP2") (pintype "bidirectional"))
      (node (ref "J2") (pin "3") (pinfunction "3_3") (pintype "bidirectional"))
      (node (ref "J2") (pin "5") (pinfunction "5_5") (pintype "bidirectional"))
      (node (ref "J4") (pin "A12_B1") (pinfunction "GND_A12_B1") (pintype "power_in"))
      (node (ref "J4") (pin "A1_B12") (pinfunction "GND_A1_B12") (pintype "power_in"))
      (node (ref "J4") (pin "SH1") (pinfunction "SHIELD_SH1") (pintype "passive"))
      (node (ref "J4") (pin "SH2") (pinfunction "SHIELD_SH2") (pintype "passive"))
      (node (ref "J4") (pin "SH3") (pinfunction "SHIELD_SH3") (pintype "passive"))
      (node (ref "J4") (pin "SH4") (pinfunction "SHIELD_SH4") (pintype "passive"))
      (node (ref "R1_USB") (pin "1") (pinfunction "1_1") (pintype "bidirectional"))
      (node (ref "R2_EP_DR") (pin "1") (pinfunction "1_1") (pintype "bidirectional"))
      (node (ref "R2_USB") (pin "2") (pinfunction "2_2") (pintype "bidirectional"))
      (node (ref "R3") (pin "1") (pinfunction "1_1") (pintype "bidirectional"))
      (node (ref "R9") (pin "1") (pinfunction "1_1") (pintype "bidirectional"))
      (node (ref "R_TYPE_SEL") (pin "1") (pinfunction "1_1") (pintype "bidirectional"))
      (node (ref "SJ1") (pin "1") (pinfunction "1_1") (pintype "passive"))
      (node (ref "SW_DN") (pin "1") (pinfunction "1_1") (pintype "passive"))
      (node (ref "SW_ENT") (pin "1") (pinfunction "1_1") (pintype "passive"))
      (node (ref "SW_UP") (pin "1") (pinfunction "1_1") (pintype "passive"))
      (node (ref "TP_BAT_GND") (pin "TP") (pinfunction "TP_TP") (pintype "input"))
      (node (ref "TP_GND") (pin "TP") (pinfunction "TP_TP") (pintype "input"))
      (node (ref "U1") (pin "P$74") (pinfunction "VSS_PAD_P$74") (pintype "bidirectional"))
      (node (ref "U1") (pin "P$75") (pinfunction "VSS_PAD_P$75") (pintype "bidirectional"))
      (node (ref "U1") (pin "P$76") (pinfunction "VSS_PAD_P$76") (pintype "bidirectional"))
      (node (ref "U1") (pin "P$77") (pinfunction "VSS_PAD_P$77") (pintype "bidirectional"))
      (node (ref "U1") (pin "P$78") (pinfunction "VSS_PAD_P$78") (pintype "bidirectional"))
      (node (ref "U1") (pin "P$79") (pinfunction "VSS_PAD_P$79") (pintype "bidirectional"))
      (node (ref "U1") (pin "P$80") (pinfunction "VSS_PAD_P$80") (pintype "bidirectional"))
      (node (ref "U1") (pin "P$81") (pinfunction "VSS_PAD_P$81") (pintype "bidirectional"))
      (node (ref "U1") (pin "P$82") (pinfunction "VSS_PAD_P$82") (pintype "bidirectional"))
      (node (ref "U1") (pin "P$83") (pinfunction "VSS_PAD_P$83") (pintype "bidirectional"))
      (node (ref "U1") (pin "P$84") (pinfunction "VSS_PAD_P$84") (pintype "bidirectional"))
      (node (ref "U1") (pin "P$85") (pinfunction "VSS_PAD_P$85") (pintype "bidirectional"))
      (node (ref "U1") (pin "P$86") (pinfunction "VSS_PAD_P$86") (pintype "bidirectional"))
      (node (ref "U1") (pin "P$87") (pinfunction "VSS_PAD_P$87") (pintype "bidirectional"))
      (node (ref "U1") (pin "P$88") (pinfunction "VSS_PAD_P$88") (pintype "bidirectional"))
      (node (ref "U1") (pin "P$89") (pinfunction "VSS_PAD_P$89") (pintype "bidirectional"))
      (node (ref "U1") (pin "P$90") (pinfunction "VSS_PAD_P$90") (pintype "bidirectional"))
      (node (ref "U1") (pin "P$B7") (pinfunction "VSS_P$B7") (pintype "power_in"))
      (node (ref "U1") (pin "P$F23") (pinfunction "VSS_PA_P$F23") (pintype "bidirectional"))
      (node (ref "U3") (pin "1") (pinfunction "CTG_1") (pintype "power_in"))
      (node (ref "U3") (pin "4") (pinfunction "GND_4") (pintype "power_in"))
      (node (ref "U3") (pin "6") (pinfunction "QSTRT_6") (pintype "input"))
      (node (ref "U3") (pin "9") (pinfunction "EP_9") (pintype "power_in"))
      (node (ref "X1") (pin "2") (pinfunction "2_2") (pintype "passive"))
      (node (ref "X1") (pin "4") (pinfunction "4_4") (pintype "passive"))
    )
    (net (code "14") (name "HAPTIC_EN") (class "Default")
      (node (ref "IC2") (pin "A1") (pinfunction "EN_A1") (pintype "bidirectional"))
      (node (ref "U1") (pin "P$U1") (pinfunction "P0.12_P$U1") (pintype "bidirectional"))
    )
    (net (code "15") (name "IMU_INT1") (class "Default")
      (node (ref "IC3") (pin "5") (pinfunction "INT1_5") (pintype "bidirectional"))
      (node (ref "U1") (pin "P$N1") (pinfunction "P0.08_P$N1") (pintype "bidirectional"))
    )
    (net (code "16") (name "IMU_INT2") (class "Default")
      (node (ref "IC3") (pin "6") (pinfunction "INT2_6") (pintype "bidirectional"))
      (node (ref "U1") (pin "P$P2") (pinfunction "P1.08_P$P2") (pintype "bidirectional"))
    )
    (net (code "17") (name "LX1") (class "Default")
      (node (ref "IC9") (pin "B2") (pinfunction "SW1_1_B2") (pintype "bidirectional"))
      (node (ref "IC9") (pin "B3") (pinfunction "SW1_2_B3") (pintype "bidirectional"))
      (node (ref "L7") (pin "1") (pinfunction "1_1") (pintype "bidirectional"))
    )
    (net (code "18") (name "LX2") (class "Default")
      (node (ref "IC9") (pin "D2") (pinfunction "SW2_1_D2") (pintype "bidirectional"))
      (node (ref "IC9") (pin "D3") (pinfunction "SW2_2_D3") (pintype "bidirectional"))
      (node (ref "L7") (pin "2") (pinfunction "2_2") (pintype "bidirectional"))
    )
    (net (code "19") (name "MOSI") (class "Default")
      (node (ref "J1") (pin "14") (pinfunction "14_14") (pintype "bidirectional"))
      (node (ref "U1") (pin "P$B13") (pinfunction "P0.03/AIN1_P$B13") (pintype "bidirectional"))
    )
    (net (code "20") (name "Net-(ANT1-FEED)") (class "Default")
      (node (ref "ANT1") (pin "1") (pinfunction "FEED_1") (pintype "input"))
      (node (ref "C22") (pin "1") (pinfunction "1_1") (pintype "passive"))
      (node (ref "C4") (pin "1") (pinfunction "1_1") (pintype "passive"))
      (node (ref "L1") (pin "2") (pinfunction "2_2") (pintype "passive"))
    )
    (net (code "21") (name "Net-(D2-K)") (class "Default")
      (node (ref "C2-EP-DR") (pin "1") (pinfunction "1_1") (pintype "passive"))
      (node (ref "D2") (pin "1") (pinfunction "K_1") (pintype "bidirectional"))
      (node (ref "D4") (pin "2") (pinfunction "A_2") (pintype "bidirectional"))
    )
    (net (code "22") (name "Net-(D5-A)") (class "Default")
      (node (ref "C2-EP-DR") (pin "2") (pinfunction "2_2") (pintype "passive"))
      (node (ref "D5") (pin "2") (pinfunction "A_2") (pintype "bidirectional"))
      (node (ref "L5") (pin "1") (pinfunction "1_1") (pintype "passive"))
      (node (ref "Q3") (pin "3") (pinfunction "D_3") (pintype "bidirectional"))
    )
    (net (code "23") (name "Net-(EPD_C1-Pad2)") (class "Default")
      (node (ref "EPD_C1") (pin "2") (pinfunction "2_2") (pintype "passive"))
      (node (ref "J1") (pin "5") (pinfunction "5_5") (pintype "bidirectional"))
    )
    (net (code "24") (name "Net-(EPD_C2-Pad2)") (class "Default")
      (node (ref "EPD_C2") (pin "2") (pinfunction "2_2") (pintype "passive"))
      (node (ref "J1") (pin "4") (pinfunction "4_4") (pintype "bidirectional"))
    )
    (net (code "25") (name "Net-(EPD_C6-Pad2)") (class "Default")
      (node (ref "EPD_C6") (pin "2") (pinfunction "2_2") (pintype "passive"))
      (node (ref "J1") (pin "18") (pinfunction "18_18") (pintype "bidirectional"))
    )
    (net (code "26") (name "Net-(EPD_C7-Pad2)") (class "Default")
      (node (ref "EPD_C7") (pin "2") (pinfunction "2_2") (pintype "passive"))
      (node (ref "J1") (pin "19") (pinfunction "19_19") (pintype "bidirectional"))
    )
    (net (code "27") (name "Net-(EPD_C8-Pad2)") (class "Default")
      (node (ref "EPD_C8") (pin "2") (pinfunction "2_2") (pintype "passive"))
      (node (ref "J1") (pin "20") (pinfunction "20_20") (pintype "bidirectional"))
    )
    (net (code "28") (name "Net-(EPD_C10-Pad2)") (class "Default")
      (node (ref "EPD_C10") (pin "2") (pinfunction "2_2") (pintype "passive"))
      (node (ref "J1") (pin "22") (pinfunction "22_22") (pintype "bidirectional"))
    )
    (net (code "29") (name "Net-(EPD_C12-Pad2)") (class "Default")
      (node (ref "EPD_C12") (pin "2") (pinfunction "2_2") (pintype "passive"))
      (node (ref "J1") (pin "24") (pinfunction "24_24") (pintype "bidirectional"))
    )
    (net (code "30") (name "Net-(IC1-TS{slash}MR)") (class "Default")
      (node (ref "IC1") (pin "D1") (pinfunction "TS/MR_D1") (pintype "bidirectional"))
      (node (ref "R9") (pin "2") (pinfunction "2_2") (pintype "bidirectional"))
    )
    (net (code "31") (name "Net-(IC2-REG)") (class "Default")
      (node (ref "C32") (pin "2") (pinfunction "2_2") (pintype "passive"))
      (node (ref "IC2") (pin "A2") (pinfunction "REG_A2") (pintype "bidirectional"))
    )
    (net (code "32") (name "Net-(IC3-SDO)") (class "Default")
      (node (ref "IC3") (pin "1") (pinfunction "SDO_1") (pintype "bidirectional"))
      (node (ref "R3") (pin "2") (pinfunction "2_2") (pintype "bidirectional"))
    )
    (net (code "33") (name "Net-(IC9-SCL)") (class "Default")
      (node (ref "IC9") (pin "D1") (pinfunction "SCL_D1") (pintype "bidirectional"))
      (node (ref "R4") (pin "2") (pinfunction "2_2") (pintype "bidirectional"))
    )
    (net (code "34") (name "Net-(IC9-SDA)") (class "Default")
      (node (ref "IC9") (pin "E1") (pinfunction "SDA_E1") (pintype "bidirectional"))
      (node (ref "R2") (pin "2") (pinfunction "2_2") (pintype "bidirectional"))
    )
    (net (code "35") (name "Net-(J4-CC1)") (class "Default")
      (node (ref "J4") (pin "A5") (pinfunction "CC1_A5") (pintype "bidirectional"))
      (node (ref "R1_USB") (pin "2") (pinfunction "2_2") (pintype "bidirectional"))
    )
    (net (code "36") (name "Net-(J4-CC2)") (class "Default")
      (node (ref "J4") (pin "B5") (pinfunction "CC2_B5") (pintype "bidirectional"))
      (node (ref "R2_USB") (pin "1") (pinfunction "1_1") (pintype "bidirectional"))
    )
    (net (code "37") (name "Net-(L2-Pad2)") (class "Default")
      (node (ref "L2") (pin "2") (pinfunction "2_2") (pintype "passive"))
      (node (ref "L3") (pin "1") (pinfunction "1_1") (pintype "passive"))
    )
    (net (code "38") (name "Net-(R1_EP_DR-Pad1)") (class "Default")
      (node (ref "R1_EP_DR") (pin "1") (pinfunction "1_1") (pintype "bidirectional"))
      (node (ref "R_TYPE_SEL") (pin "2") (pinfunction "2_2") (pintype "bidirectional"))
      (node (ref "SJ1") (pin "2") (pinfunction "2_2") (pintype "passive"))
    )
    (net (code "39") (name "Net-(U1-ANT)") (class "Default")
      (node (ref "C3") (pin "1") (pinfunction "1_1") (pintype "passive"))
      (node (ref "L1") (pin "1") (pinfunction "1_1") (pintype "passive"))
      (node (ref "U1") (pin "P$H23") (pinfunction "ANT_P$H23") (pintype "bidirectional"))
    )
    (net (code "40") (name "Net-(U1-DCC)") (class "Default")
      (node (ref "L2") (pin "1") (pinfunction "1_1") (pintype "passive"))
      (node (ref "U1") (pin "P$B3") (pinfunction "DCC_P$B3") (pintype "output"))
    )
    (net (code "41") (name "Net-(U1-DEC1)") (class "Default")
      (node (ref "C5") (pin "1") (pinfunction "1_1") (pintype "passive"))
      (node (ref "U1") (pin "P$C1") (pinfunction "DEC1_P$C1") (pintype "power_in"))
    )
    (net (code "42") (name "Net-(U1-DEC2)") (class "Default")
      (node (ref "C13") (pin "1") (pinfunction "1_1") (pintype "passive"))
      (node (ref "U1") (pin "P$A18") (pinfunction "DEC2_P$A18") (pintype "bidirectional"))
    )
    (net (code "43") (name "Net-(U1-DEC3)") (class "Default")
      (node (ref "C11") (pin "1") (pinfunction "1_1") (pintype "passive"))
      (node (ref "U1") (pin "P$D23") (pinfunction "DEC3_P$D23") (pintype "bidirectional"))
    )
    (net (code "44") (name "Net-(U1-DEC3V3)") (class "Default")
      (node (ref "C20") (pin "1") (pinfunction "1_1") (pintype "passive"))
      (node (ref "U1") (pin "P$AC5") (pinfunction "DEC3V3_P$AC5") (pintype "bidirectional"))
    )
    (net (code "45") (name "Net-(U1-DEC4)") (class "Default")
      (node (ref "C10") (pin "1") (pinfunction "1_1") (pintype "passive"))
      (node (ref "C15") (pin "1") (pinfunction "1_1") (pintype "passive"))
      (node (ref "C16") (pin "1") (pinfunction "1_1") (pintype "passive"))
      (node (ref "L3") (pin "2") (pinfunction "2_2") (pintype "passive"))
      (node (ref "U1") (pin "P$B5") (pinfunction "DEC4_P$B5") (pintype "power_in"))
      (node (ref "U1") (pin "P$E24") (pinfunction "DEC6_P$E24") (pintype "bidirectional"))
    )
    (net (code "46") (name "Net-(U1-DEC5)") (class "Default")
      (node (ref "C9") (pin "1") (pinfunction "1_1") (pintype "passive"))
      (node (ref "U1") (pin "P$N24") (pinfunction "DEC5_P$N24") (pintype "bidirectional"))
    )
    (net (code "47") (name "Net-(U1-P0.00{slash}XL1)") (class "Default")
      (node (ref "C17") (pin "2") (pinfunction "2_2") (pintype "passive"))
      (node (ref "U1") (pin "P$D2") (pinfunction "P0.00/XL1_P$D2") (pintype "bidirectional"))
      (node (ref "X2") (pin "2") (pinfunction "2_2") (pintype "passive"))
    )
    (net (code "48") (name "Net-(U1-P0.01{slash}XL2)") (class "Default")
      (node (ref "C18") (pin "2") (pinfunction "2_2") (pintype "passive"))
      (node (ref "U1") (pin "P$F2") (pinfunction "P0.01/XL2_P$F2") (pintype "bidirectional"))
      (node (ref "X2") (pin "1") (pinfunction "1_1") (pintype "passive"))
    )
    (net (code "49") (name "Net-(U1-XC1)") (class "Default")
      (node (ref "C1") (pin "1") (pinfunction "1_1") (pintype "passive"))
      (node (ref "U1") (pin "P$B24") (pinfunction "XC1_P$B24") (pintype "input"))
      (node (ref "X1") (pin "1") (pinfunction "1_1") (pintype "passive"))
    )
    (net (code "50") (name "Net-(U1-XC2)") (class "Default")
      (node (ref "C2") (pin "1") (pinfunction "1_1") (pintype "passive"))
      (node (ref "U1") (pin "P$A23") (pinfunction "XC2_P$A23") (pintype "output"))
      (node (ref "X1") (pin "3") (pinfunction "3_3") (pintype "passive"))
    )
    (net (code "51") (name "OUT+") (class "Default")
      (node (ref "IC2") (pin "A3") (pinfunction "OUT+_A3") (pintype "bidirectional"))
      (node (ref "TP_OP") (pin "TP") (pinfunction "TP_TP") (pintype "input"))
    )
    (net (code "52") (name "OUT-") (class "Default")
      (node (ref "IC2") (pin "C3") (pinfunction "OUT-_C3") (pintype "bidirectional"))
      (node (ref "TP_ON") (pin "TP") (pinfunction "TP_TP") (pintype "input"))
    )
    (net (code "53") (name "P0.04") (class "Default")
      (node (ref "U1") (pin "P$J1") (pinfunction "P0.04/AIN2_P$J1") (pintype "bidirectional"))
    )
    (net (code "54") (name "P0.09") (class "Default")
      (node (ref "U1") (pin "P$L24") (pinfunction "P0.09/NFC1_P$L24") (pintype "bidirectional"))
    )
    (net (code "55") (name "P0.13") (class "Default")
      (node (ref "C30") (pin "2") (pinfunction "2_2") (pintype "passive"))
      (node (ref "R5") (pin "1") (pinfunction "1_1") (pintype "bidirectional"))
      (node (ref "SW_UP") (pin "2") (pinfunction "2_2") (pintype "passive"))
      (node (ref "U1") (pin "P$AD8") (pinfunction "P0.13_P$AD8") (pintype "bidirectional"))
    )
    (net (code "56") (name "P0.14") (class "Default")
      (node (ref "C31") (pin "2") (pinfunction "2_2") (pintype "passive"))
      (node (ref "R8") (pin "1") (pinfunction "1_1") (pintype "bidirectional"))
      (node (ref "SW_ENT") (pin "2") (pinfunction "2_2") (pintype "passive"))
      (node (ref "U1") (pin "P$AC9") (pinfunction "P0.14_P$AC9") (pintype "bidirectional"))
    )
    (net (code "57") (name "P0.19") (class "Default")
      (node (ref "U1") (pin "P$AC15") (pinfunction "P0.19_P$AC15") (pintype "bidirectional"))
    )
    (net (code "58") (name "P0.20") (class "Default")
      (node (ref "U1") (pin "P$AD16") (pinfunction "P0.20_P$AD16") (pintype "bidirectional"))
    )
    (net (code "59") (name "P0.21") (class "Default")
      (node (ref "U1") (pin "P$AC17") (pinfunction "P0.21_P$AC17") (pintype "bidirectional"))
    )
    (net (code "60") (name "P0.22") (class "Default")
      (node (ref "U1") (pin "P$AD18") (pinfunction "P0.22_P$AD18") (pintype "bidirectional"))
    )
    (net (code "61") (name "P0.23") (class "Default")
      (node (ref "U1") (pin "P$AC19") (pinfunction "P0.23_P$AC19") (pintype "bidirectional"))
    )
    (net (code "62") (name "P0.24") (class "Default")
      (node (ref "U1") (pin "P$AD20") (pinfunction "P0.24_P$AD20") (pintype "bidirectional"))
    )
    (net (code "63") (name "P0.25") (class "Default")
      (node (ref "U1") (pin "P$AC21") (pinfunction "P0.25_P$AC21") (pintype "bidirectional"))
    )
    (net (code "64") (name "P0.26") (class "Default")
      (node (ref "U1") (pin "P$G1") (pinfunction "P0.26_P$G1") (pintype "bidirectional"))
    )
    (net (code "65") (name "P0.27") (class "Default")
      (node (ref "U1") (pin "P$H2") (pinfunction "P0.27_P$H2") (pintype "bidirectional"))
    )
    (net (code "66") (name "P0.28") (class "Default")
      (node (ref "U1") (pin "P$B11") (pinfunction "P0.28/AIN4_P$B11") (pintype "bidirectional"))
    )
    (net (code "67") (name "P0.29") (class "Default")
      (node (ref "U1") (pin "P$A10") (pinfunction "P0.29/AIN5_P$A10") (pintype "bidirectional"))
    )
    (net (code "68") (name "P0.30") (class "Default")
      (node (ref "U1") (pin "P$B9") (pinfunction "P0.30/AIN6_P$B9") (pintype "bidirectional"))
    )
    (net (code "69") (name "P0.31") (class "Default")
      (node (ref "U1") (pin "P$A8") (pinfunction "P0.31/AIN7_P$A8") (pintype "bidirectional"))
    )
    (net (code "70") (name "P1.01") (class "Default")
      (node (ref "Q1") (pin "1") (pinfunction "G_1") (pintype "bidirectional"))
      (node (ref "R_PWR_EPD") (pin "1") (pinfunction "1_1") (pintype "bidirectional"))
      (node (ref "U1") (pin "P$Y23") (pinfunction "P1.01_P$Y23") (pintype "bidirectional"))
    )
    (net (code "71") (name "P1.02") (class "Default")
      (node (ref "C29") (pin "2") (pinfunction "2_2") (pintype "passive"))
      (node (ref "R7") (pin "1") (pinfunction "1_1") (pintype "bidirectional"))
      (node (ref "SW_DN") (pin "2") (pinfunction "2_2") (pintype "passive"))
      (node (ref "U1") (pin "P$W24") (pinfunction "P1.02_P$W24") (pintype "bidirectional"))
    )
    (net (code "72") (name "P1.03") (class "Default")
      (node (ref "U1") (pin "P$V23") (pinfunction "P1.03_P$V23") (pintype "bidirectional"))
    )
    (net (code "73") (name "P1.04") (class "Default")
      (node (ref "U1") (pin "P$U24") (pinfunction "P1.04_P$U24") (pintype "bidirectional"))
    )
    (net (code "74") (name "P1.05") (class "Default")
      (node (ref "U1") (pin "P$T23") (pinfunction "P1.05_P$T23") (pintype "bidirectional"))
    )
    (net (code "75") (name "P1.06") (class "Default")
      (node (ref "U1") (pin "P$R24") (pinfunction "P1.06_P$R24") (pintype "bidirectional"))
    )
    (net (code "76") (name "P1.07") (class "Default")
      (node (ref "U1") (pin "P$P23") (pinfunction "P1.07_P$P23") (pintype "bidirectional"))
    )
    (net (code "77") (name "P1.09") (class "Default")
      (node (ref "U1") (pin "P$R1") (pinfunction "P1.09_P$R1") (pintype "bidirectional"))
    )
    (net (code "78") (name "P1.10") (class "Default")
      (node (ref "U1") (pin "P$A20") (pinfunction "P1.10_P$A20") (pintype "bidirectional"))
    )
    (net (code "79") (name "P1.11") (class "Default")
      (node (ref "U1") (pin "P$B19") (pinfunction "P1.11_P$B19") (pintype "bidirectional"))
    )
    (net (code "80") (name "P1.12") (class "Default")
      (node (ref "U1") (pin "P$B17") (pinfunction "P1.12_P$B17") (pintype "bidirectional"))
    )
    (net (code "81") (name "P1.13") (class "Default")
      (node (ref "U1") (pin "P$A16") (pinfunction "P1.13_P$A16") (pintype "bidirectional"))
    )
    (net (code "82") (name "P1.14") (class "Default")
      (node (ref "U1") (pin "P$B15") (pinfunction "P1.14_P$B15") (pintype "bidirectional"))
    )
    (net (code "83") (name "P1.15") (class "Default")
      (node (ref "U1") (pin "P$A14") (pinfunction "P1.15_P$A14") (pintype "bidirectional"))
    )
    (net (code "84") (name "PMIC_INT") (class "Default")
      (node (ref "IC1") (pin "A1") (pinfunction "~{INT}_A1") (pintype "bidirectional"))
      (node (ref "U1") (pin "P$T2") (pinfunction "P0.11_P$T2") (pintype "bidirectional"))
    )
    (net (code "85") (name "PREVGH") (class "Default")
      (node (ref "D5") (pin "1") (pinfunction "K_1") (pintype "bidirectional"))
      (node (ref "EPD_C9") (pin "2") (pinfunction "2_2") (pintype "passive"))
      (node (ref "J1") (pin "21") (pinfunction "21_21") (pintype "bidirectional"))
    )
    (net (code "86") (name "PREVGL") (class "Default")
      (node (ref "D2") (pin "2") (pinfunction "A_2") (pintype "bidirectional"))
      (node (ref "EPD_C11") (pin "2") (pinfunction "2_2") (pintype "passive"))
      (node (ref "J1") (pin "23") (pinfunction "23_23") (pintype "bidirectional"))
    )
    (net (code "87") (name "RESE") (class "Default")
      (node (ref "J1") (pin "3") (pinfunction "3_3") (pintype "bidirectional"))
      (node (ref "Q3") (pin "2") (pinfunction "S_2") (pintype "bidirectional"))
      (node (ref "R1_EP_DR") (pin "2") (pinfunction "2_2") (pintype "bidirectional"))
    )
    (net (code "88") (name "RESET") (class "Default")
      (node (ref "J2") (pin "6") (pinfunction "6_6") (pintype "bidirectional"))
      (node (ref "TP_RESET") (pin "TP") (pinfunction "TP_TP") (pintype "input"))
      (node (ref "U1") (pin "P$AC13") (pinfunction "P0.18/RESET_P$AC13") (pintype "bidirectional"))
    )
    (net (code "89") (name "SCK") (class "Default")
      (node (ref "J1") (pin "13") (pinfunction "13_13") (pintype "bidirectional"))
      (node (ref "U1") (pin "P$A12") (pinfunction "P0.02/AIN0_P$A12") (pintype "bidirectional"))
    )
    (net (code "90") (name "SCL") (class "Default")
      (node (ref "IC1") (pin "B1") (pinfunction "SCL_B1") (pintype "bidirectional"))
      (node (ref "IC2") (pin "C1") (pinfunction "SCL_C1") (pintype "bidirectional"))
      (node (ref "IC3") (pin "12") (pinfunction "SCX_12") (pintype "bidirectional"))
      (node (ref "R17") (pin "2") (pinfunction "2_2") (pintype "bidirectional"))
      (node (ref "R4") (pin "1") (pinfunction "1_1") (pintype "bidirectional"))
      (node (ref "TP_SCL") (pin "TP") (pinfunction "TP_TP") (pintype "input"))
      (node (ref "U1") (pin "P$M2") (pinfunction "P0.07_P$M2") (pintype "bidirectional"))
      (node (ref "U3") (pin "7") (pinfunction "SCL_7") (pintype "input"))
    )
    (net (code "91") (name "SDA") (class "Default")
      (node (ref "IC1") (pin "C1") (pinfunction "SDA_C1") (pintype "bidirectional"))
      (node (ref "IC2") (pin "B2") (pinfunction "SDA_B2") (pintype "bidirectional"))
      (node (ref "IC3") (pin "2") (pinfunction "SDX_2") (pintype "bidirectional"))
      (node (ref "R18") (pin "2") (pinfunction "2_2") (pintype "bidirectional"))
      (node (ref "R2") (pin "1") (pinfunction "1_1") (pintype "bidirectional"))
      (node (ref "TP_SDA") (pin "TP") (pinfunction "TP_TP") (pintype "input"))
      (node (ref "U1") (pin "P$L1") (pinfunction "P0.06_P$L1") (pintype "bidirectional"))
      (node (ref "U3") (pin "8") (pinfunction "SDA_8") (pintype "bidirectional"))
    )
    (net (code "92") (name "SWDCLK") (class "Default")
      (node (ref "J2") (pin "4") (pinfunction "4_4") (pintype "bidirectional"))
      (node (ref "TP_SWDCLK") (pin "TP") (pinfunction "TP_TP") (pintype "input"))
      (node (ref "U1") (pin "P$AA24") (pinfunction "SWDCLK_P$AA24") (pintype "input"))
    )
    (net (code "93") (name "SWDIO") (class "Default")
      (node (ref "J2") (pin "2") (pinfunction "2_2") (pintype "bidirectional"))
      (node (ref "TP_SWDIO") (pin "TP") (pinfunction "TP_TP") (pintype "input"))
      (node (ref "U1") (pin "P$AC24") (pinfunction "SWDIO_P$AC24") (pintype "bidirectional"))
    )
    (net (code "94") (name "SWO") (class "Default")
      (node (ref "TP_SWO") (pin "TP") (pinfunction "TP_TP") (pintype "input"))
      (node (ref "U1") (pin "P$AD22") (pinfunction "P1.00_P$AD22") (pintype "bidirectional"))
    )
    (net (code "95") (name "VBAT") (class "Default")
      (node (ref "C27") (pin "2") (pinfunction "2_2") (pintype "passive"))
      (node (ref "C37") (pin "2") (pinfunction "2_2") (pintype "passive"))
      (node (ref "IC1") (pin "C2") (pinfunction "BAT_C2") (pintype "bidirectional"))
      (node (ref "TP_VBAT") (pin "TP") (pinfunction "TP_TP") (pintype "input"))
      (node (ref "U3") (pin "2") (pinfunction "CELL_2") (pintype "power_in"))
      (node (ref "U3") (pin "3") (pinfunction "VDD_3") (pintype "power_in"))
    )
    (net (code "96") (name "VBUS") (class "Default")
      (node (ref "C21") (pin "1") (pinfunction "1_1") (pintype "passive"))
      (node (ref "C38") (pin "2") (pinfunction "2_2") (pintype "passive"))
      (node (ref "C42") (pin "1") (pinfunction "1_1") (pintype "passive"))
      (node (ref "C43") (pin "1") (pinfunction "1_1") (pintype "passive"))
      (node (ref "D3") (pin "5") (pinfunction "VBUS_5") (pintype "bidirectional"))
      (node (ref "IC1") (pin "A2") (pinfunction "IN_A2") (pintype "bidirectional"))
      (node (ref "J4") (pin "A4_B9") (pinfunction "VBUS_A4_B9") (pintype "power_in"))
      (node (ref "J4") (pin "A9_B4") (pinfunction "VBUS_A9_B4") (pintype "power_in"))
      (node (ref "U1") (pin "P$AD2") (pinfunction "VBUS_P$AD2") (pintype "power_in"))
    )
    (net (code "97") (name "VREG") (class "Default")
      (node (ref "C23") (pin "2") (pinfunction "2_2") (pintype "passive"))
      (node (ref "C24") (pin "2") (pinfunction "2_2") (pintype "passive"))
      (node (ref "C39") (pin "1") (pinfunction "1_1") (pintype "passive"))
      (node (ref "IC1") (pin "B2") (pinfunction "SYS_B2") (pintype "bidirectional"))
      (node (ref "IC9") (pin "A1") (pinfunction "EN_A1") (pintype "bidirectional"))
      (node (ref "IC9") (pin "A2") (pinfunction "VIN_1_A2") (pintype "bidirectional"))
      (node (ref "IC9") (pin "A3") (pinfunction "VIN_2_A3") (pintype "bidirectional"))
      (node (ref "TP_VREG") (pin "TP") (pinfunction "TP_TP") (pintype "input"))
    )
    (net (code "98") (name "unconnected-(ANT1-NC-Pad2)") (class "Default")
      (node (ref "ANT1") (pin "2") (pinfunction "NC_2") (pintype "no_connect"))
    )
    (net (code "99") (name "unconnected-(IC3-ASCL-Pad11)") (class "Default")
      (node (ref "IC3") (pin "11") (pinfunction "ASCL_11") (pintype "bidirectional"))
    )
    (net (code "100") (name "unconnected-(IC3-ASDA-Pad4)") (class "Default")
      (node (ref "IC3") (pin "4") (pinfunction "ASDA_4") (pintype "bidirectional"))
    )
    (net (code "101") (name "unconnected-(J1-Pad1)") (class "Default")
      (node (ref "J1") (pin "1") (pinfunction "1_1") (pintype "bidirectional"))
    )
    (net (code "102") (name "unconnected-(J1-Pad6)") (class "Default")
      (node (ref "J1") (pin "6") (pinfunction "6_6") (pintype "bidirectional"))
    )
    (net (code "103") (name "unconnected-(J1-Pad7)") (class "Default")
      (node (ref "J1") (pin "7") (pinfunction "7_7") (pintype "bidirectional"))
    )
    (net (code "104") (name "unconnected-(J4-SBU1-PadA8)") (class "Default")
      (node (ref "J4") (pin "A8") (pinfunction "SBU1_A8") (pintype "bidirectional"))
    )
    (net (code "105") (name "unconnected-(J4-SBU2-PadB8)") (class "Default")
      (node (ref "J4") (pin "B8") (pinfunction "SBU2_B8") (pintype "bidirectional"))
    )
    (net (code "106") (name "unconnected-(U1-DCCH-PadP$AB2)") (class "Default")
      (node (ref "U1") (pin "P$AB2") (pinfunction "DCCH_P$AB2") (pintype "bidirectional"))
    )
  )
)
